# muxed.net
KiCad netlist of a schematic drawn in EAGLE
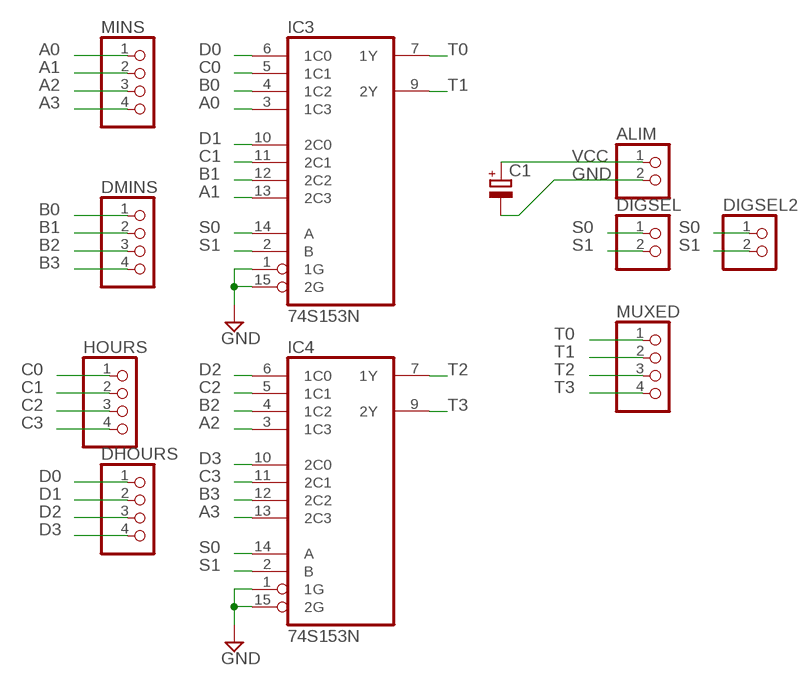
[diagram p0: schematic, sheet 1]

(export (version "E")
  (design (tool "Eeschema 10.0.6"))
  (components
    (comp (ref "ALIM")
      (value "PINHD-1X2")
      (footprint "eagle-import:1X02")
      (libsource (lib "eagle-import") (part "PINHD-1X2"))
    )
    (comp (ref "C1")
      (value "CPOL-EUE2-5")
      (footprint "eagle-import:E2-5")
      (libsource (lib "eagle-import") (part "CPOL-EUE2-5"))
    )
    (comp (ref "DHOURS")
      (value "PINHD-1X4")
      (footprint "eagle-import:1X04")
      (libsource (lib "eagle-import") (part "PINHD-1X4"))
    )
    (comp (ref "DIGSEL")
      (value "PINHD-1X2")
      (footprint "eagle-import:1X02")
      (libsource (lib "eagle-import") (part "PINHD-1X2"))
    )
    (comp (ref "DIGSEL2")
      (value "PINHD-1X2")
      (footprint "eagle-import:1X02")
      (libsource (lib "eagle-import") (part "PINHD-1X2"))
    )
    (comp (ref "DMINS")
      (value "PINHD-1X4")
      (footprint "eagle-import:1X04")
      (libsource (lib "eagle-import") (part "PINHD-1X4"))
    )
    (comp (ref "HOURS")
      (value "PINHD-1X4")
      (footprint "eagle-import:1X04")
      (libsource (lib "eagle-import") (part "PINHD-1X4"))
    )
    (comp (ref "IC3")
      (value "74S153N")
      (footprint "eagle-import:DIL16")
      (libsource (lib "eagle-import") (part "74153NS"))
    )
    (comp (ref "IC4")
      (value "74S153N")
      (footprint "eagle-import:DIL16")
      (libsource (lib "eagle-import") (part "74153NS"))
    )
    (comp (ref "MINS")
      (value "PINHD-1X4")
      (footprint "eagle-import:1X04")
      (libsource (lib "eagle-import") (part "PINHD-1X4"))
    )
    (comp (ref "MUXED")
      (value "PINHD-1X4")
      (footprint "eagle-import:1X04")
      (libsource (lib "eagle-import") (part "PINHD-1X4"))
    )
  )
  (nets
    (net (code "1") (name "/A0") (class "Default")
      (node (ref "IC3") (pin "3") (pinfunction "1C3_3") (pintype "input"))
      (node (ref "MINS") (pin "1") (pinfunction "1_1") (pintype "passive"))
    )
    (net (code "2") (name "/A1") (class "Default")
      (node (ref "IC3") (pin "13") (pinfunction "2C3_13") (pintype "input"))
      (node (ref "MINS") (pin "2") (pinfunction "2_2") (pintype "passive"))
    )
    (net (code "3") (name "/A2") (class "Default")
      (node (ref "IC4") (pin "3") (pinfunction "1C3_3") (pintype "input"))
      (node (ref "MINS") (pin "3") (pinfunction "3_3") (pintype "passive"))
    )
    (net (code "4") (name "/A3") (class "Default")
      (node (ref "IC4") (pin "13") (pinfunction "2C3_13") (pintype "input"))
      (node (ref "MINS") (pin "4") (pinfunction "4_4") (pintype "passive"))
    )
    (net (code "5") (name "/B0") (class "Default")
      (node (ref "DMINS") (pin "1") (pinfunction "1_1") (pintype "passive"))
      (node (ref "IC3") (pin "4") (pinfunction "1C2_4") (pintype "input"))
    )
    (net (code "6") (name "/B1") (class "Default")
      (node (ref "DMINS") (pin "2") (pinfunction "2_2") (pintype "passive"))
      (node (ref "IC3") (pin "12") (pinfunction "2C2_12") (pintype "input"))
    )
    (net (code "7") (name "/B2") (class "Default")
      (node (ref "DMINS") (pin "3") (pinfunction "3_3") (pintype "passive"))
      (node (ref "IC4") (pin "4") (pinfunction "1C2_4") (pintype "input"))
    )
    (net (code "8") (name "/B3") (class "Default")
      (node (ref "DMINS") (pin "4") (pinfunction "4_4") (pintype "passive"))
      (node (ref "IC4") (pin "12") (pinfunction "2C2_12") (pintype "input"))
    )
    (net (code "9") (name "/C0") (class "Default")
      (node (ref "HOURS") (pin "1") (pinfunction "1_1") (pintype "passive"))
      (node (ref "IC3") (pin "5") (pinfunction "1C1_5") (pintype "input"))
    )
    (net (code "10") (name "/C1") (class "Default")
      (node (ref "HOURS") (pin "2") (pinfunction "2_2") (pintype "passive"))
      (node (ref "IC3") (pin "11") (pinfunction "2C1_11") (pintype "input"))
    )
    (net (code "11") (name "/C2") (class "Default")
      (node (ref "HOURS") (pin "3") (pinfunction "3_3") (pintype "passive"))
      (node (ref "IC4") (pin "5") (pinfunction "1C1_5") (pintype "input"))
    )
    (net (code "12") (name "/C3") (class "Default")
      (node (ref "HOURS") (pin "4") (pinfunction "4_4") (pintype "passive"))
      (node (ref "IC4") (pin "11") (pinfunction "2C1_11") (pintype "input"))
    )
    (net (code "13") (name "/D0") (class "Default")
      (node (ref "DHOURS") (pin "1") (pinfunction "1_1") (pintype "passive"))
      (node (ref "IC3") (pin "6") (pinfunction "1C0_6") (pintype "input"))
    )
    (net (code "14") (name "/D1") (class "Default")
      (node (ref "DHOURS") (pin "2") (pinfunction "2_2") (pintype "passive"))
      (node (ref "IC3") (pin "10") (pinfunction "2C0_10") (pintype "input"))
    )
    (net (code "15") (name "/D2") (class "Default")
      (node (ref "DHOURS") (pin "3") (pinfunction "3_3") (pintype "passive"))
      (node (ref "IC4") (pin "6") (pinfunction "1C0_6") (pintype "input"))
    )
    (net (code "16") (name "/D3") (class "Default")
      (node (ref "DHOURS") (pin "4") (pinfunction "4_4") (pintype "passive"))
      (node (ref "IC4") (pin "10") (pinfunction "2C0_10") (pintype "input"))
    )
    (net (code "17") (name "/S0") (class "Default")
      (node (ref "DIGSEL") (pin "1") (pinfunction "1_1") (pintype "passive"))
      (node (ref "DIGSEL2") (pin "1") (pinfunction "1_1") (pintype "passive"))
      (node (ref "IC3") (pin "14") (pinfunction "A_14") (pintype "input"))
      (node (ref "IC4") (pin "14") (pinfunction "A_14") (pintype "input"))
    )
    (net (code "18") (name "/S1") (class "Default")
      (node (ref "DIGSEL") (pin "2") (pinfunction "2_2") (pintype "passive"))
      (node (ref "DIGSEL2") (pin "2") (pinfunction "2_2") (pintype "passive"))
      (node (ref "IC3") (pin "2") (pinfunction "B_2") (pintype "input"))
      (node (ref "IC4") (pin "2") (pinfunction "B_2") (pintype "input"))
    )
    (net (code "19") (name "/T0") (class "Default")
      (node (ref "IC3") (pin "7") (pinfunction "1Y_7") (pintype "output"))
      (node (ref "MUXED") (pin "1") (pinfunction "1_1") (pintype "passive"))
    )
    (net (code "20") (name "/T1") (class "Default")
      (node (ref "IC3") (pin "9") (pinfunction "2Y_9") (pintype "output"))
      (node (ref "MUXED") (pin "2") (pinfunction "2_2") (pintype "passive"))
    )
    (net (code "21") (name "/T2") (class "Default")
      (node (ref "IC4") (pin "7") (pinfunction "1Y_7") (pintype "output"))
      (node (ref "MUXED") (pin "3") (pinfunction "3_3") (pintype "passive"))
    )
    (net (code "22") (name "/T3") (class "Default")
      (node (ref "IC4") (pin "9") (pinfunction "2Y_9") (pintype "output"))
      (node (ref "MUXED") (pin "4") (pinfunction "4_4") (pintype "passive"))
    )
    (net (code "23") (name "/VCC") (class "Default")
      (node (ref "ALIM") (pin "1") (pinfunction "1_1") (pintype "passive"))
      (node (ref "C1") (pin "+") (pinfunction "+_+") (pintype "passive"))
    )
    (net (code "24") (name "GND") (class "Default")
      (node (ref "ALIM") (pin "2") (pinfunction "2_2") (pintype "passive"))
      (node (ref "C1") (pin "-") (pinfunction "-_-") (pintype "passive"))
      (node (ref "IC3") (pin "1") (pinfunction "1G_1") (pintype "input"))
      (node (ref "IC3") (pin "15") (pinfunction "2G_15") (pintype "input"))
      (node (ref "IC4") (pin "1") (pinfunction "1G_1") (pintype "input"))
      (node (ref "IC4") (pin "15") (pinfunction "2G_15") (pintype "input"))
    )
  )
)
